# ps.net
KiCad netlist of a schematic drawn in EAGLE
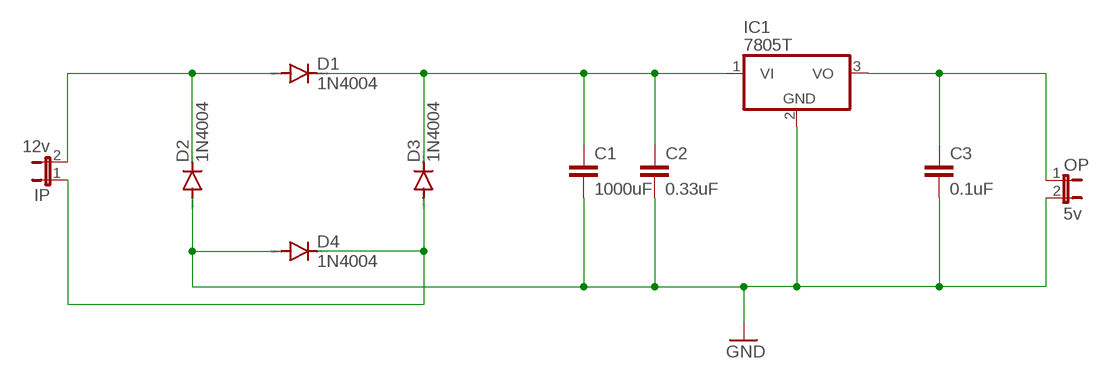
[diagram p0: schematic, sheet 1]

(export (version "E")
  (design (tool "Eeschema 10.0.6"))
  (components
    (comp (ref "C1")
      (value "1000uF")
      (footprint "eagle-import:C2.5-3")
      (libsource (lib "eagle-import") (part "C2,5-3"))
    )
    (comp (ref "C2")
      (value "0.33uF")
      (footprint "eagle-import:C2.5-3")
      (libsource (lib "eagle-import") (part "C2,5-3"))
    )
    (comp (ref "C3")
      (value "0.1uF")
      (footprint "eagle-import:C2.5-3")
      (libsource (lib "eagle-import") (part "C2,5-3"))
    )
    (comp (ref "D1")
      (value "1N4004")
      (footprint "eagle-import:DO41-10")
      (libsource (lib "eagle-import") (part "1N4004"))
    )
    (comp (ref "D2")
      (value "1N4004")
      (footprint "eagle-import:DO41-10")
      (libsource (lib "eagle-import") (part "1N4004"))
    )
    (comp (ref "D3")
      (value "1N4004")
      (footprint "eagle-import:DO41-10")
      (libsource (lib "eagle-import") (part "1N4004"))
    )
    (comp (ref "D4")
      (value "1N4004")
      (footprint "eagle-import:DO41-10")
      (libsource (lib "eagle-import") (part "1N4004"))
    )
    (comp (ref "IC1")
      (value "7805T")
      (footprint "eagle-import:TO220H")
      (libsource (lib "eagle-import") (part "78T05"))
    )
    (comp (ref "IP")
      (value "12v")
      (footprint "eagle-import:JP1")
      (libsource (lib "eagle-import") (part "JP1E"))
    )
    (comp (ref "OP")
      (value "5v")
      (footprint "eagle-import:JP1")
      (libsource (lib "eagle-import") (part "JP1E"))
    )
  )
  (nets
    (net (code "1") (name "GND") (class "Default")
      (node (ref "C1") (pin "2") (pinfunction "2_2") (pintype "passive"))
      (node (ref "C2") (pin "2") (pinfunction "2_2") (pintype "passive"))
      (node (ref "C3") (pin "2") (pinfunction "2_2") (pintype "passive"))
      (node (ref "D2") (pin "A") (pinfunction "A_A") (pintype "passive"))
      (node (ref "D4") (pin "A") (pinfunction "A_A") (pintype "passive"))
      (node (ref "IC1") (pin "2") (pinfunction "GND_2") (pintype "passive"))
      (node (ref "OP") (pin "2") (pinfunction "2_2") (pintype "passive"))
    )
    (net (code "2") (name "Net-(D1-PadA)") (class "Default")
      (node (ref "D1") (pin "A") (pinfunction "A_A") (pintype "passive"))
      (node (ref "D2") (pin "C") (pinfunction "C_C") (pintype "passive"))
      (node (ref "IP") (pin "2") (pinfunction "2_2") (pintype "passive"))
    )
    (net (code "3") (name "Net-(D3-PadA)") (class "Default")
      (node (ref "D3") (pin "A") (pinfunction "A_A") (pintype "passive"))
      (node (ref "D4") (pin "C") (pinfunction "C_C") (pintype "passive"))
      (node (ref "IP") (pin "1") (pinfunction "1_1") (pintype "passive"))
    )
    (net (code "4") (name "Net-(IC1-VI)") (class "Default")
      (node (ref "C1") (pin "1") (pinfunction "1_1") (pintype "passive"))
      (node (ref "C2") (pin "1") (pinfunction "1_1") (pintype "passive"))
      (node (ref "D1") (pin "C") (pinfunction "C_C") (pintype "passive"))
      (node (ref "D3") (pin "C") (pinfunction "C_C") (pintype "passive"))
      (node (ref "IC1") (pin "1") (pinfunction "VI_1") (pintype "input"))
    )
    (net (code "5") (name "Net-(IC1-VO)") (class "Default")
      (node (ref "C3") (pin "1") (pinfunction "1_1") (pintype "passive"))
      (node (ref "IC1") (pin "3") (pinfunction "VO_3") (pintype "passive"))
      (node (ref "OP") (pin "1") (pinfunction "1_1") (pintype "passive"))
    )
  )
)
